# Main.net
KiCad netlist of a schematic drawn in Altium Designer
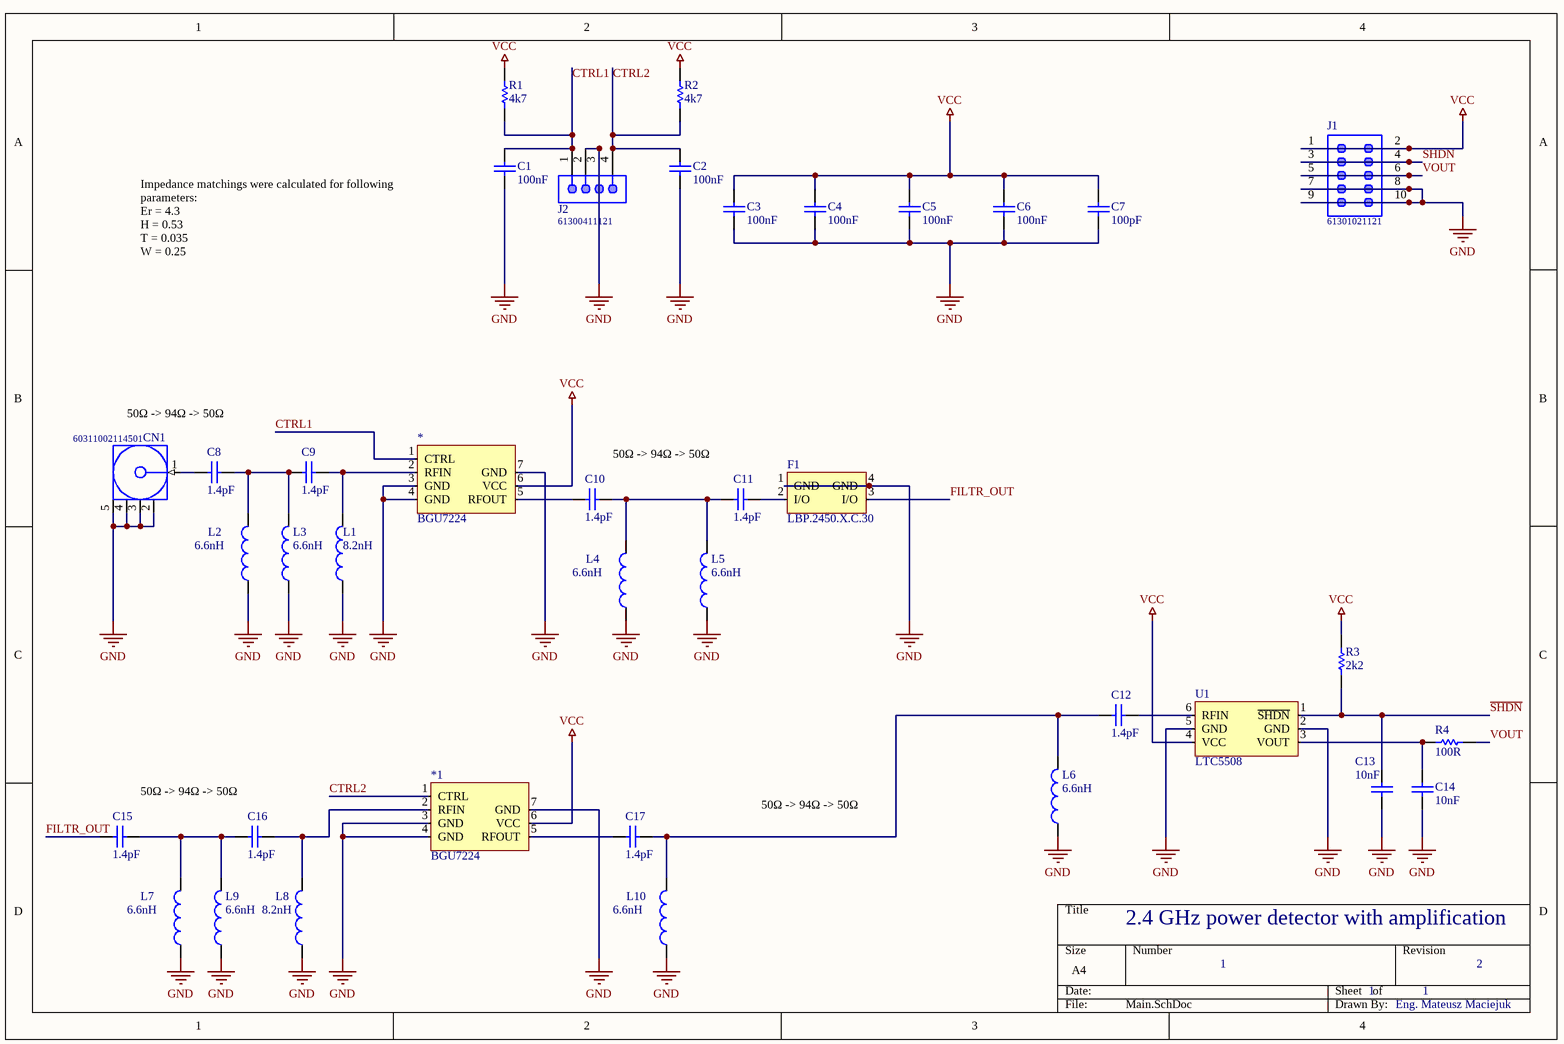
[diagram p0: Main.SchDoc]

(export (version "E")
  (design (tool "Eeschema 10.0.6"))
  (components
    (comp (ref "*")
      (value "BGU7224")
      (footprint "SON50P160X50_HS-7M")
      (libsource (lib "Schlib1") (part "BGU7224"))
    )
    (comp (ref "*1")
      (value "BGU7224")
      (footprint "SON50P160X50_HS-7M")
      (libsource (lib "Schlib1") (part "BGU7224"))
    )
    (comp (ref "C1")
      (value "100nF")
      (footprint "CAPC0402(1005)60_M")
      (description "CAP 100nF 50V ±20% 0402 (1005 Metric) Thickness 0.6mm SMD")
      (fields (field (name "TOLERANCE") "Â±20%"))
      (libsource (lib "Altium Content Vault") (part "CAP"))
    )
    (comp (ref "C2")
      (value "100nF")
      (footprint "CAPC0402(1005)60_M")
      (description "CAP 100nF 50V ±20% 0402 (1005 Metric) Thickness 0.6mm SMD")
      (fields (field (name "TOLERANCE") "Â±20%"))
      (libsource (lib "Altium Content Vault") (part "CAP"))
    )
    (comp (ref "C3")
      (value "100nF")
      (footprint "CAPC0402(1005)60_M")
      (description "CAP 100nF 50V ±20% 0402 (1005 Metric) Thickness 0.6mm SMD")
      (fields (field (name "TOLERANCE") "Â±20%"))
      (libsource (lib "Altium Content Vault") (part "CAP"))
    )
    (comp (ref "C4")
      (value "100nF")
      (footprint "CAPC0402(1005)60_M")
      (description "CAP 100nF 50V ±20% 0402 (1005 Metric) Thickness 0.6mm SMD")
      (fields (field (name "TOLERANCE") "Â±20%"))
      (libsource (lib "Altium Content Vault") (part "CAP"))
    )
    (comp (ref "C5")
      (value "100nF")
      (footprint "CAPC0402(1005)60_M")
      (description "CAP 100nF 50V ±20% 0402 (1005 Metric) Thickness 0.6mm SMD")
      (fields (field (name "TOLERANCE") "Â±20%"))
      (libsource (lib "Altium Content Vault") (part "CAP"))
    )
    (comp (ref "C6")
      (value "100nF")
      (footprint "CAPC0402(1005)60_M")
      (description "CAP 100nF 50V ±20% 0402 (1005 Metric) Thickness 0.6mm SMD")
      (fields (field (name "TOLERANCE") "Â±20%"))
      (libsource (lib "Altium Content Vault") (part "CAP"))
    )
    (comp (ref "C7")
      (value "100pF")
      (footprint "CAPC0402(1005)60_M")
      (description "CAP 100nF 50V ±20% 0402 (1005 Metric) Thickness 0.6mm SMD")
      (fields (field (name "TOLERANCE") "Â±20%"))
      (libsource (lib "Altium Content Vault") (part "CAP"))
    )
    (comp (ref "C8")
      (value "1.4pF")
      (footprint "CAPC0402(1005)60_M")
      (description "CAP 100nF 50V ±20% 0402 (1005 Metric) Thickness 0.6mm SMD")
      (fields (field (name "TOLERANCE") "Â±20%"))
      (libsource (lib "Altium Content Vault") (part "CAP"))
    )
    (comp (ref "C9")
      (value "1.4pF")
      (footprint "CAPC0402(1005)60_M")
      (description "CAP 100nF 50V ±20% 0402 (1005 Metric) Thickness 0.6mm SMD")
      (fields (field (name "TOLERANCE") "Â±20%"))
      (libsource (lib "Altium Content Vault") (part "CAP"))
    )
    (comp (ref "C10")
      (value "1.4pF")
      (footprint "CAPC0402(1005)60_M")
      (description "CAP 100nF 50V ±20% 0402 (1005 Metric) Thickness 0.6mm SMD")
      (fields (field (name "TOLERANCE") "Â±20%"))
      (libsource (lib "Altium Content Vault") (part "CAP"))
    )
    (comp (ref "C11")
      (value "1.4pF")
      (footprint "CAPC0402(1005)60_M")
      (description "CAP 100nF 50V ±20% 0402 (1005 Metric) Thickness 0.6mm SMD")
      (fields (field (name "TOLERANCE") "Â±20%"))
      (libsource (lib "Altium Content Vault") (part "CAP"))
    )
    (comp (ref "C12")
      (value "1.4pF")
      (footprint "CAPC0402(1005)60_M")
      (description "CAP 100nF 50V ±20% 0402 (1005 Metric) Thickness 0.6mm SMD")
      (fields (field (name "TOLERANCE") "Â±20%"))
      (libsource (lib "Altium Content Vault") (part "CAP"))
    )
    (comp (ref "C13")
      (value "10nF")
      (footprint "WCAP-CSGP_0603_Reflow")
      (description "WCAP-CSGP General Purpose Ceramic Capacitors, size 0603, 100nF, +/-10%, 10VDC")
      (fields (field (name "PART NUMBER") "885012206020") (field (name "PUBLISHER") "Wurth Elektronik"))
      (libsource (lib "885012006035_Altium_WCAP-CSGP_rev19a") (part "885012206020"))
    )
    (comp (ref "C14")
      (value "10nF")
      (footprint "WCAP-CSGP_0603_Reflow")
      (description "WCAP-CSGP General Purpose Ceramic Capacitors, size 0603, 100nF, +/-10%, 10VDC")
      (fields (field (name "PART NUMBER") "885012206020") (field (name "PUBLISHER") "Wurth Elektronik"))
      (libsource (lib "885012006035_Altium_WCAP-CSGP_rev19a") (part "885012206020"))
    )
    (comp (ref "C15")
      (value "1.4pF")
      (footprint "CAPC0402(1005)60_M")
      (description "CAP 100nF 50V ±20% 0402 (1005 Metric) Thickness 0.6mm SMD")
      (fields (field (name "TOLERANCE") "Â±20%"))
      (libsource (lib "Altium Content Vault") (part "CAP"))
    )
    (comp (ref "C16")
      (value "1.4pF")
      (footprint "CAPC0402(1005)60_M")
      (description "CAP 100nF 50V ±20% 0402 (1005 Metric) Thickness 0.6mm SMD")
      (fields (field (name "TOLERANCE") "Â±20%"))
      (libsource (lib "Altium Content Vault") (part "CAP"))
    )
    (comp (ref "C17")
      (value "1.4pF")
      (footprint "CAPC0402(1005)60_M")
      (description "CAP 100nF 50V ±20% 0402 (1005 Metric) Thickness 0.6mm SMD")
      (fields (field (name "TOLERANCE") "Â±20%"))
      (libsource (lib "Altium Content Vault") (part "CAP"))
    )
    (comp (ref "CN1")
      (value "60311002114501")
      (footprint "60311002114501")
      (description "WR-SMA PCB Jack, THT, Right Angle")
      (fields (field (name "PUBLISHER") "Wurth Elektronik"))
      (libsource (lib "60311002114501_Altium_WR-SMA_rev19a") (part "60311002114501"))
    )
    (comp (ref "F1")
      (value "LBP.2450.X.C.30")
      (footprint "LBP.2450.X.C.30")
      (libsource (lib "Schlib1") (part "LBP.2450.X.C.30"))
    )
    (comp (ref "J1")
      (value "61301021121")
      (footprint "61301021121")
      (description "WR-PHD Pin Header, THT, pitch 2.54mm, Dual Row, Vertical, 10pin")
      (fields (field (name "PUBLISHER") "Wurth Elektronik"))
      (libsource (lib "61300411121_Altium_WR-PHD_rev19a") (part "61301021121"))
    )
    (comp (ref "J2")
      (value "61300411121")
      (footprint "61300411121")
      (description "WR-PHD Pin Header, THT, pitch 2.54mm, Single Row, Vertical, 4pin")
      (fields (field (name "PUBLISHER") "Wurth Elektronik"))
      (libsource (lib "61300411121_Altium_WR-PHD_rev19a") (part "61300411121"))
    )
    (comp (ref "L1")
      (value "8.2nH")
      (footprint "INDC1006X60X20LL10T10")
      (description "Chip Inductor, 8.2 nH, +/- 5%, 500 mA, -55 to 125 degC, 0402 (1005 Metric), RoHS, Tape and Reel")
      (fields (field (name "MANUFACTURER") "Murata"))
      (libsource (lib "Altium Content Vault") (part "IND-2"))
    )
    (comp (ref "L2")
      (value "6.6nH")
      (footprint "INDC1006X60X20LL10T10")
      (description "Chip Inductor, 6.6 nH, +/- 5%, 500 mA, -55 to 125 degC, 0402 (1005 Metric), RoHS, Tape and Reel")
      (fields (field (name "MANUFACTURER") "Murata"))
      (libsource (lib "Altium Content Vault") (part "IND-2"))
    )
    (comp (ref "L3")
      (value "6.6nH")
      (footprint "INDC1006X60X20LL10T10")
      (description "Chip Inductor, 6.6 nH, +/- 5%, 500 mA, -55 to 125 degC, 0402 (1005 Metric), RoHS, Tape and Reel")
      (fields (field (name "MANUFACTURER") "Murata"))
      (libsource (lib "Altium Content Vault") (part "IND-2"))
    )
    (comp (ref "L4")
      (value "6.6nH")
      (footprint "INDC1006X60X20LL10T10")
      (description "Chip Inductor, 6.6 nH, +/- 5%, 500 mA, -55 to 125 degC, 0402 (1005 Metric), RoHS, Tape and Reel")
      (fields (field (name "MANUFACTURER") "Murata"))
      (libsource (lib "Altium Content Vault") (part "IND-2"))
    )
    (comp (ref "L5")
      (value "6.6nH")
      (footprint "INDC1006X60X20LL10T10")
      (description "Chip Inductor, 6.6 nH, +/- 5%, 500 mA, -55 to 125 degC, 0402 (1005 Metric), RoHS, Tape and Reel")
      (fields (field (name "MANUFACTURER") "Murata"))
      (libsource (lib "Altium Content Vault") (part "IND-2"))
    )
    (comp (ref "L6")
      (value "6.6nH")
      (footprint "INDC1006X60X20LL10T10")
      (description "Chip Inductor, 6.6 nH, +/- 5%, 500 mA, -55 to 125 degC, 0402 (1005 Metric), RoHS, Tape and Reel")
      (fields (field (name "MANUFACTURER") "Murata"))
      (libsource (lib "Altium Content Vault") (part "IND-2"))
    )
    (comp (ref "L7")
      (value "6.6nH")
      (footprint "INDC1006X60X20LL10T10")
      (description "Chip Inductor, 6.6 nH, +/- 5%, 500 mA, -55 to 125 degC, 0402 (1005 Metric), RoHS, Tape and Reel")
      (fields (field (name "MANUFACTURER") "Murata"))
      (libsource (lib "Altium Content Vault") (part "IND-2"))
    )
    (comp (ref "L8")
      (value "8.2nH")
      (footprint "INDC1006X60X20LL10T10")
      (description "Chip Inductor, 8.2 nH, +/- 5%, 500 mA, -55 to 125 degC, 0402 (1005 Metric), RoHS, Tape and Reel")
      (fields (field (name "MANUFACTURER") "Murata"))
      (libsource (lib "Altium Content Vault") (part "IND-2"))
    )
    (comp (ref "L9")
      (value "6.6nH")
      (footprint "INDC1006X60X20LL10T10")
      (description "Chip Inductor, 6.6 nH, +/- 5%, 500 mA, -55 to 125 degC, 0402 (1005 Metric), RoHS, Tape and Reel")
      (fields (field (name "MANUFACTURER") "Murata"))
      (libsource (lib "Altium Content Vault") (part "IND-2"))
    )
    (comp (ref "L10")
      (value "6.6nH")
      (footprint "INDC1006X60X20LL10T10")
      (description "Chip Inductor, 6.6 nH, +/- 5%, 500 mA, -55 to 125 degC, 0402 (1005 Metric), RoHS, Tape and Reel")
      (fields (field (name "MANUFACTURER") "Murata"))
      (libsource (lib "Altium Content Vault") (part "IND-2"))
    )
    (comp (ref "R1")
      (value "4k7")
      (footprint "RESC1005X40X25ML05T05")
      (fields (field (name "PART NUMBER") "CRCW04022K20FKED") (field (name "MANUFACTURER") "Vishay Dale"))
      (libsource (lib "Altium Content Vault") (part "RES"))
    )
    (comp (ref "R2")
      (value "4k7")
      (footprint "RESC1005X40X25ML05T05")
      (fields (field (name "PART NUMBER") "CRCW04022K20FKED") (field (name "MANUFACTURER") "Vishay Dale"))
      (libsource (lib "Altium Content Vault") (part "RES"))
    )
    (comp (ref "R3")
      (value "2k2")
      (footprint "RESC1005X40X25ML05T05")
      (fields (field (name "PART NUMBER") "CRCW04022K20FKED") (field (name "MANUFACTURER") "Vishay Dale"))
      (libsource (lib "Altium Content Vault") (part "RES"))
    )
    (comp (ref "R4")
      (value "100R")
      (footprint "RESC1005X40X25ML05T05")
      (fields (field (name "PART NUMBER") "CRCW04022K20FKED") (field (name "MANUFACTURER") "Vishay Dale"))
      (libsource (lib "Altium Content Vault") (part "RES"))
    )
    (comp (ref "U1")
      (value "LTC5508")
      (footprint "SOT65P210X100-6N")
      (libsource (lib "Schlib1") (part "LTC5508"))
    )
  )
  (nets
    (net (code "1") (name "/CTRL1") (class "Default")
      (node (ref "*") (pin "1") (pinfunction "CTRL_1") (pintype "bidirectional"))
      (node (ref "C1") (pin "2") (pinfunction "2_2") (pintype "passive"))
      (node (ref "J2") (pin "1") (pinfunction "1_1") (pintype "passive"))
      (node (ref "R1") (pin "1") (pinfunction "1_1") (pintype "passive"))
    )
    (net (code "2") (name "/CTRL2") (class "Default")
      (node (ref "*1") (pin "1") (pinfunction "CTRL_1") (pintype "bidirectional"))
      (node (ref "C2") (pin "2") (pinfunction "2_2") (pintype "passive"))
      (node (ref "J2") (pin "4") (pinfunction "4_4") (pintype "passive"))
      (node (ref "R2") (pin "1") (pinfunction "1_1") (pintype "passive"))
    )
    (net (code "3") (name "/FILTR_OUT") (class "Default")
      (node (ref "C15") (pin "1") (pinfunction "1_1") (pintype "passive"))
      (node (ref "F1") (pin "3") (pinfunction "I/O_3") (pintype "bidirectional"))
    )
    (net (code "4") (name "/VOUT") (class "Default")
      (node (ref "J1") (pin "5") (pinfunction "5_5") (pintype "passive"))
      (node (ref "J1") (pin "6") (pinfunction "6_6") (pintype "passive"))
      (node (ref "R4") (pin "1") (pinfunction "1_1") (pintype "passive"))
    )
    (net (code "5") (name "/~{SHDN}") (class "Default")
      (node (ref "C13") (pin "2") (pinfunction "2_2") (pintype "passive"))
      (node (ref "J1") (pin "3") (pinfunction "3_3") (pintype "passive"))
      (node (ref "J1") (pin "4") (pinfunction "4_4") (pintype "passive"))
      (node (ref "R3") (pin "1") (pinfunction "1_1") (pintype "passive"))
      (node (ref "U1") (pin "1") (pinfunction "~{SHDN}_1") (pintype "bidirectional"))
    )
    (net (code "6") (name "GND") (class "Default")
      (node (ref "*") (pin "3") (pinfunction "GND_3") (pintype "bidirectional"))
      (node (ref "*") (pin "4") (pinfunction "GND_4") (pintype "bidirectional"))
      (node (ref "*") (pin "7") (pinfunction "GND_7") (pintype "bidirectional"))
      (node (ref "*1") (pin "3") (pinfunction "GND_3") (pintype "bidirectional"))
      (node (ref "*1") (pin "4") (pinfunction "GND_4") (pintype "bidirectional"))
      (node (ref "*1") (pin "7") (pinfunction "GND_7") (pintype "bidirectional"))
      (node (ref "C1") (pin "1") (pinfunction "1_1") (pintype "passive"))
      (node (ref "C13") (pin "1") (pinfunction "1_1") (pintype "passive"))
      (node (ref "C14") (pin "1") (pinfunction "1_1") (pintype "passive"))
      (node (ref "C2") (pin "1") (pinfunction "1_1") (pintype "passive"))
      (node (ref "C3") (pin "2") (pinfunction "2_2") (pintype "passive"))
      (node (ref "C4") (pin "2") (pinfunction "2_2") (pintype "passive"))
      (node (ref "C5") (pin "2") (pinfunction "2_2") (pintype "passive"))
      (node (ref "C6") (pin "2") (pinfunction "2_2") (pintype "passive"))
      (node (ref "C7") (pin "2") (pinfunction "2_2") (pintype "passive"))
      (node (ref "CN1") (pin "2") (pinfunction "GND_2") (pintype "power_in"))
      (node (ref "CN1") (pin "3") (pinfunction "GND_3") (pintype "power_in"))
      (node (ref "CN1") (pin "4") (pinfunction "GND_4") (pintype "power_in"))
      (node (ref "CN1") (pin "5") (pinfunction "GND_5") (pintype "power_in"))
      (node (ref "F1") (pin "1") (pinfunction "GND_1") (pintype "bidirectional"))
      (node (ref "F1") (pin "4") (pinfunction "GND_4") (pintype "bidirectional"))
      (node (ref "J1") (pin "10") (pinfunction "10_10") (pintype "passive"))
      (node (ref "J1") (pin "7") (pinfunction "7_7") (pintype "passive"))
      (node (ref "J1") (pin "8") (pinfunction "8_8") (pintype "passive"))
      (node (ref "J1") (pin "9") (pinfunction "9_9") (pintype "passive"))
      (node (ref "J2") (pin "2") (pinfunction "2_2") (pintype "passive"))
      (node (ref "J2") (pin "3") (pinfunction "3_3") (pintype "passive"))
      (node (ref "L1") (pin "1") (pinfunction "1_1") (pintype "passive"))
      (node (ref "L10") (pin "1") (pinfunction "1_1") (pintype "passive"))
      (node (ref "L2") (pin "1") (pinfunction "1_1") (pintype "passive"))
      (node (ref "L3") (pin "1") (pinfunction "1_1") (pintype "passive"))
      (node (ref "L4") (pin "1") (pinfunction "1_1") (pintype "passive"))
      (node (ref "L5") (pin "1") (pinfunction "1_1") (pintype "passive"))
      (node (ref "L6") (pin "1") (pinfunction "1_1") (pintype "passive"))
      (node (ref "L7") (pin "1") (pinfunction "1_1") (pintype "passive"))
      (node (ref "L8") (pin "1") (pinfunction "1_1") (pintype "passive"))
      (node (ref "L9") (pin "1") (pinfunction "1_1") (pintype "passive"))
      (node (ref "U1") (pin "2") (pinfunction "GND_2") (pintype "bidirectional"))
      (node (ref "U1") (pin "5") (pinfunction "GND_5") (pintype "bidirectional"))
    )
    (net (code "7") (name "Net-(*-RFIN)") (class "Default")
      (node (ref "*") (pin "2") (pinfunction "RFIN_2") (pintype "bidirectional"))
      (node (ref "C9") (pin "1") (pinfunction "1_1") (pintype "passive"))
      (node (ref "L1") (pin "2") (pinfunction "2_2") (pintype "passive"))
    )
    (net (code "8") (name "Net-(*-RFOUT)") (class "Default")
      (node (ref "*") (pin "5") (pinfunction "RFOUT_5") (pintype "bidirectional"))
      (node (ref "C10") (pin "1") (pinfunction "1_1") (pintype "passive"))
    )
    (net (code "9") (name "Net-(*1-RFIN)") (class "Default")
      (node (ref "*1") (pin "2") (pinfunction "RFIN_2") (pintype "bidirectional"))
      (node (ref "C16") (pin "1") (pinfunction "1_1") (pintype "passive"))
      (node (ref "L8") (pin "2") (pinfunction "2_2") (pintype "passive"))
    )
    (net (code "10") (name "Net-(*1-RFOUT)") (class "Default")
      (node (ref "*1") (pin "5") (pinfunction "RFOUT_5") (pintype "bidirectional"))
      (node (ref "C17") (pin "1") (pinfunction "1_1") (pintype "passive"))
    )
    (net (code "11") (name "Net-(C8-Pad2)") (class "Default")
      (node (ref "C8") (pin "2") (pinfunction "2_2") (pintype "passive"))
      (node (ref "C9") (pin "2") (pinfunction "2_2") (pintype "passive"))
      (node (ref "L2") (pin "2") (pinfunction "2_2") (pintype "passive"))
      (node (ref "L3") (pin "2") (pinfunction "2_2") (pintype "passive"))
    )
    (net (code "12") (name "Net-(C10-Pad2)") (class "Default")
      (node (ref "C10") (pin "2") (pinfunction "2_2") (pintype "passive"))
      (node (ref "C11") (pin "2") (pinfunction "2_2") (pintype "passive"))
      (node (ref "L4") (pin "2") (pinfunction "2_2") (pintype "passive"))
      (node (ref "L5") (pin "2") (pinfunction "2_2") (pintype "passive"))
    )
    (net (code "13") (name "Net-(C11-Pad1)") (class "Default")
      (node (ref "C11") (pin "1") (pinfunction "1_1") (pintype "passive"))
      (node (ref "F1") (pin "2") (pinfunction "I/O_2") (pintype "bidirectional"))
    )
    (net (code "14") (name "Net-(C12-Pad2)") (class "Default")
      (node (ref "C12") (pin "2") (pinfunction "2_2") (pintype "passive"))
      (node (ref "C17") (pin "2") (pinfunction "2_2") (pintype "passive"))
      (node (ref "L10") (pin "2") (pinfunction "2_2") (pintype "passive"))
      (node (ref "L6") (pin "2") (pinfunction "2_2") (pintype "passive"))
    )
    (net (code "15") (name "Net-(C15-Pad2)") (class "Default")
      (node (ref "C15") (pin "2") (pinfunction "2_2") (pintype "passive"))
      (node (ref "C16") (pin "2") (pinfunction "2_2") (pintype "passive"))
      (node (ref "L7") (pin "2") (pinfunction "2_2") (pintype "passive"))
      (node (ref "L9") (pin "2") (pinfunction "2_2") (pintype "passive"))
    )
    (net (code "16") (name "Net-(CN1-Signal)") (class "Default")
      (node (ref "C8") (pin "1") (pinfunction "1_1") (pintype "passive"))
      (node (ref "CN1") (pin "1") (pinfunction "Signal_1") (pintype "input"))
    )
    (net (code "17") (name "Net-(U1-RFIN)") (class "Default")
      (node (ref "C12") (pin "1") (pinfunction "1_1") (pintype "passive"))
      (node (ref "U1") (pin "6") (pinfunction "RFIN_6") (pintype "bidirectional"))
    )
    (net (code "18") (name "Net-(U1-VOUT)") (class "Default")
      (node (ref "C14") (pin "2") (pinfunction "2_2") (pintype "passive"))
      (node (ref "R4") (pin "2") (pinfunction "2_2") (pintype "passive"))
      (node (ref "U1") (pin "3") (pinfunction "VOUT_3") (pintype "bidirectional"))
    )
    (net (code "19") (name "VCC") (class "Default")
      (node (ref "*") (pin "6") (pinfunction "VCC_6") (pintype "bidirectional"))
      (node (ref "*1") (pin "6") (pinfunction "VCC_6") (pintype "bidirectional"))
      (node (ref "C3") (pin "1") (pinfunction "1_1") (pintype "passive"))
      (node (ref "C4") (pin "1") (pinfunction "1_1") (pintype "passive"))
      (node (ref "C5") (pin "1") (pinfunction "1_1") (pintype "passive"))
      (node (ref "C6") (pin "1") (pinfunction "1_1") (pintype "passive"))
      (node (ref "C7") (pin "1") (pinfunction "1_1") (pintype "passive"))
      (node (ref "J1") (pin "1") (pinfunction "1_1") (pintype "passive"))
      (node (ref "J1") (pin "2") (pinfunction "2_2") (pintype "passive"))
      (node (ref "R1") (pin "2") (pinfunction "2_2") (pintype "passive"))
      (node (ref "R2") (pin "2") (pinfunction "2_2") (pintype "passive"))
      (node (ref "R3") (pin "2") (pinfunction "2_2") (pintype "passive"))
      (node (ref "U1") (pin "4") (pinfunction "VCC_4") (pintype "bidirectional"))
    )
  )
)
